# BBiQ-1_2.net
KiCad netlist of a schematic drawn in EAGLE
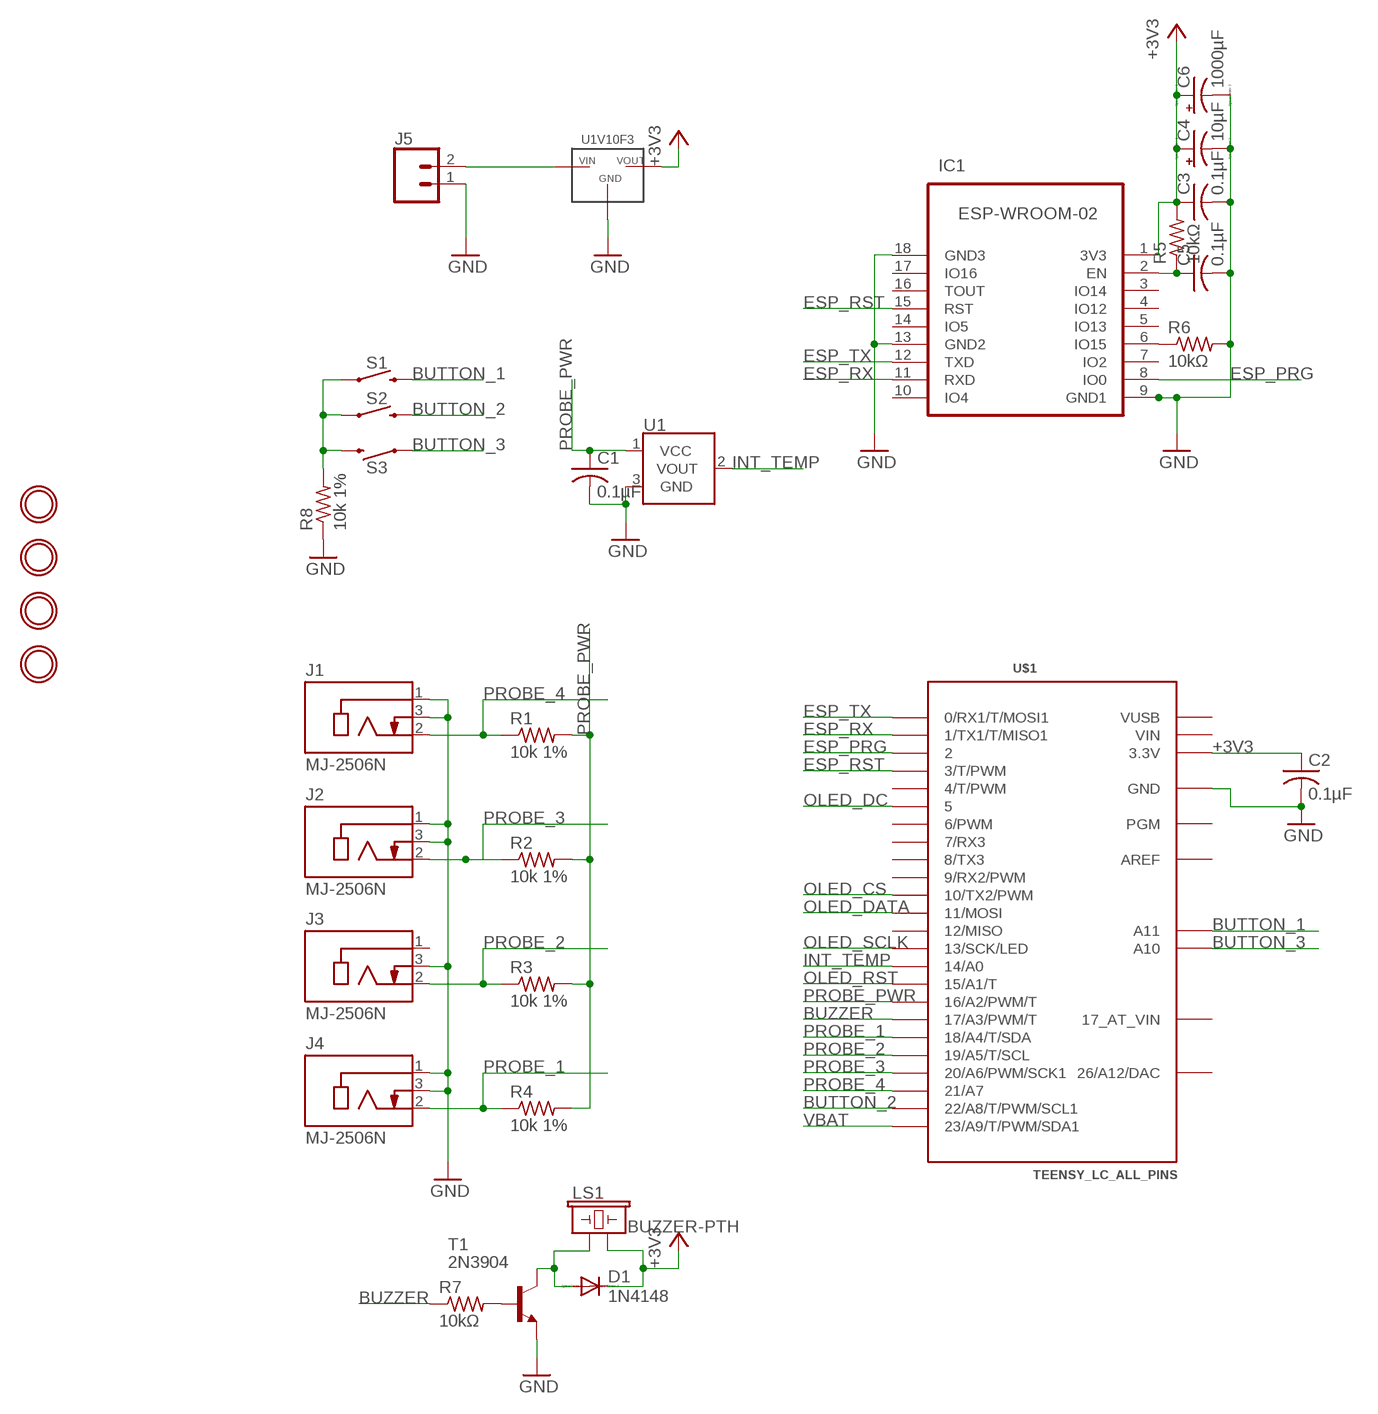
[diagram p0: schematic, sheet 1]

(export (version "E")
  (design (tool "Eeschema 10.0.6"))
  (components
    (comp (ref "C1")
      (value "0.1µF")
      (footprint "eagle-import:C025-025X050")
      (libsource (lib "eagle-import") (part "C-US025-025X050"))
    )
    (comp (ref "C2")
      (value "0.1µF")
      (footprint "eagle-import:C025-025X050")
      (libsource (lib "eagle-import") (part "C-US025-025X050"))
    )
    (comp (ref "C3")
      (value "0.1µF")
      (footprint "eagle-import:C025-025X050")
      (libsource (lib "eagle-import") (part "C-US025-025X050"))
    )
    (comp (ref "C4")
      (value "10µF")
      (footprint "eagle-import:E2-5")
      (libsource (lib "eagle-import") (part "CPOL-USE2-5"))
    )
    (comp (ref "C5")
      (value "0.1µF")
      (footprint "eagle-import:C025-025X050")
      (libsource (lib "eagle-import") (part "C-US025-025X050"))
    )
    (comp (ref "C6")
      (value "1000µF")
      (footprint "eagle-import:E3,5-8")
      (libsource (lib "eagle-import") (part "CPOL-USE3.5-8"))
    )
    (comp (ref "D1")
      (value "1N4148")
      (footprint "eagle-import:DO35-7")
      (libsource (lib "eagle-import") (part "1N4148DO35-7"))
    )
    (comp (ref "IC1")
      (value "ESP-WROOM-02")
      (footprint "eagle-import:ESP-WROOM-02")
      (libsource (lib "eagle-import") (part "ESP-WROOM-02"))
    )
    (comp (ref "J1")
      (value "MJ-2506N")
      (footprint "eagle-import:CUI_MJ-2506N")
      (fields (field (name "MANUFACTURER") "CUI INC"))
      (libsource (lib "eagle-import") (part "MJ-2506N"))
    )
    (comp (ref "J2")
      (value "MJ-2506N")
      (footprint "eagle-import:CUI_MJ-2506N")
      (fields (field (name "MANUFACTURER") "CUI INC"))
      (libsource (lib "eagle-import") (part "MJ-2506N"))
    )
    (comp (ref "J3")
      (value "MJ-2506N")
      (footprint "eagle-import:CUI_MJ-2506N")
      (fields (field (name "MANUFACTURER") "CUI INC"))
      (libsource (lib "eagle-import") (part "MJ-2506N"))
    )
    (comp (ref "J4")
      (value "MJ-2506N")
      (footprint "eagle-import:CUI_MJ-2506N")
      (fields (field (name "MANUFACTURER") "CUI INC"))
      (libsource (lib "eagle-import") (part "MJ-2506N"))
    )
    (comp (ref "J5")
      (value "CONN_02JST-PTH-2")
      (footprint "eagle-import:JST-2-PTH")
      (libsource (lib "eagle-import") (part "CONN_02JST-PTH-2"))
    )
    (comp (ref "LS1")
      (value "BUZZER-PTH")
      (footprint "eagle-import:BUZZER-12MM")
      (libsource (lib "eagle-import") (part "BUZZER-PTH"))
    )
    (comp (ref "R1")
      (value "10k 1%")
      (footprint "eagle-import:0207_7")
      (libsource (lib "eagle-import") (part "R-US_0207/7"))
    )
    (comp (ref "R2")
      (value "10k 1%")
      (footprint "eagle-import:0207_7")
      (libsource (lib "eagle-import") (part "R-US_0207/7"))
    )
    (comp (ref "R3")
      (value "10k 1%")
      (footprint "eagle-import:0207_7")
      (libsource (lib "eagle-import") (part "R-US_0207/7"))
    )
    (comp (ref "R4")
      (value "10k 1%")
      (footprint "eagle-import:0207_7")
      (libsource (lib "eagle-import") (part "R-US_0207/7"))
    )
    (comp (ref "R5")
      (value "10kΩ")
      (footprint "eagle-import:0207_7")
      (libsource (lib "eagle-import") (part "R-US_0207/7"))
    )
    (comp (ref "R6")
      (value "10kΩ")
      (footprint "eagle-import:0207_7")
      (libsource (lib "eagle-import") (part "R-US_0207/7"))
    )
    (comp (ref "R7")
      (value "10kΩ")
      (footprint "eagle-import:0207_7")
      (libsource (lib "eagle-import") (part "R-US_0207/7"))
    )
    (comp (ref "R8")
      (value "10k 1%")
      (footprint "eagle-import:0207_7")
      (libsource (lib "eagle-import") (part "R-US_0207/7"))
    )
    (comp (ref "S1")
      (value "MOMENTARY-SWITCH-SPST-PTH-6.0MM")
      (footprint "eagle-import:TACTILE_SWITCH_PTH_6.0MM")
      (libsource (lib "eagle-import") (part "MOMENTARY-SWITCH-SPST-PTH-6.0MM"))
    )
    (comp (ref "S2")
      (value "MOMENTARY-SWITCH-SPST-PTH-6.0MM")
      (footprint "eagle-import:TACTILE_SWITCH_PTH_6.0MM")
      (libsource (lib "eagle-import") (part "MOMENTARY-SWITCH-SPST-PTH-6.0MM"))
    )
    (comp (ref "S3")
      (value "MOMENTARY-SWITCH-SPST-PTH-6.0MM")
      (footprint "eagle-import:TACTILE_SWITCH_PTH_6.0MM")
      (libsource (lib "eagle-import") (part "MOMENTARY-SWITCH-SPST-PTH-6.0MM"))
    )
    (comp (ref "T1")
      (value "2N3904")
      (footprint "eagle-import:TO92")
      (libsource (lib "eagle-import") (part "2N3904"))
    )
    (comp (ref "U$1")
      (value "TEENSY_LC_ALL_PINS")
      (footprint "eagle-import:TEENSY_3.0-3.2&LC_ALL_PINS")
      (libsource (lib "eagle-import") (part "TEENSY_LC_ALL_PINS"))
    )
    (comp (ref "U$2")
      (value "U1V10F3")
      (footprint "eagle-import:U1V10F3")
      (libsource (lib "eagle-import") (part "U1V10F3"))
    )
    (comp (ref "U$3")
      (value "MOUNTINGHOLE2.5")
      (footprint "eagle-import:MOUNTINGHOLE_2.5_PLATED")
      (libsource (lib "eagle-import") (part "MOUNTINGHOLE2.5"))
    )
    (comp (ref "U$4")
      (value "MOUNTINGHOLE2.5")
      (footprint "eagle-import:MOUNTINGHOLE_2.5_PLATED")
      (libsource (lib "eagle-import") (part "MOUNTINGHOLE2.5"))
    )
    (comp (ref "U$5")
      (value "MOUNTINGHOLE2.5")
      (footprint "eagle-import:MOUNTINGHOLE_2.5_PLATED")
      (libsource (lib "eagle-import") (part "MOUNTINGHOLE2.5"))
    )
    (comp (ref "U$6")
      (value "MOUNTINGHOLE2.5")
      (footprint "eagle-import:MOUNTINGHOLE_2.5_PLATED")
      (libsource (lib "eagle-import") (part "MOUNTINGHOLE2.5"))
    )
    (comp (ref "U1")
      (value "TMP36GT9")
      (footprint "eagle-import:TO-92")
      (libsource (lib "eagle-import") (part "TMP36GT9"))
    )
  )
  (nets
    (net (code "1") (name "+3V3") (class "Default")
      (node (ref "C2") (pin "1") (pinfunction "1_1") (pintype "passive"))
      (node (ref "C3") (pin "1") (pinfunction "1_1") (pintype "passive"))
      (node (ref "C4") (pin "+") (pinfunction "+_+") (pintype "passive"))
      (node (ref "C6") (pin "+") (pinfunction "+_+") (pintype "passive"))
      (node (ref "D1") (pin "C") (pinfunction "C_C") (pintype "passive"))
      (node (ref "IC1") (pin "1") (pinfunction "3V3_1") (pintype "power_in"))
      (node (ref "LS1") (pin "-") (pinfunction "2_-") (pintype "passive"))
      (node (ref "R5") (pin "2") (pinfunction "2_2") (pintype "passive"))
      (node (ref "U$1") (pin "3.3V") (pinfunction "3.3V_3.3V") (pintype "power_in"))
      (node (ref "U$1") (pin "3.3V1") (pinfunction "3.3V_3.3V1") (pintype "power_in"))
      (node (ref "U$2") (pin "VOUT") (pinfunction "VOUT_VOUT") (pintype "bidirectional"))
    )
    (net (code "2") (name "/26{slash}A12{slash}DAC") (class "Default")
      (node (ref "U$1") (pin "RESET/DAC") (pinfunction "26/A12/DAC_RESET/DAC") (pintype "power_in"))
    )
    (net (code "3") (name "/AREF") (class "Default")
      (node (ref "U$1") (pin "AREF") (pinfunction "AREF_AREF") (pintype "power_in"))
    )
    (net (code "4") (name "/BUTTON_1") (class "Default")
      (node (ref "S1") (pin "3") (pinfunction "2_3") (pintype "passive"))
      (node (ref "U$1") (pin "A11") (pinfunction "A11_A11") (pintype "bidirectional"))
    )
    (net (code "5") (name "/BUTTON_2") (class "Default")
      (node (ref "S2") (pin "3") (pinfunction "2_3") (pintype "passive"))
      (node (ref "U$1") (pin "22/A8") (pinfunction "22/A8/T/PWM/SCL1_22/A8") (pintype "bidirectional"))
    )
    (net (code "6") (name "/BUTTON_3") (class "Default")
      (node (ref "S3") (pin "1") (pinfunction "1_1") (pintype "passive"))
      (node (ref "U$1") (pin "A10") (pinfunction "A10_A10") (pintype "bidirectional"))
    )
    (net (code "7") (name "/BUZZER") (class "Default")
      (node (ref "R7") (pin "1") (pinfunction "1_1") (pintype "passive"))
      (node (ref "U$1") (pin "17/A3") (pinfunction "17/A3/PWM/T_17/A3") (pintype "bidirectional"))
    )
    (net (code "8") (name "/ESP_PRG") (class "Default")
      (node (ref "IC1") (pin "8") (pinfunction "IO0_8") (pintype "bidirectional"))
      (node (ref "U$1") (pin "2") (pinfunction "2_2") (pintype "bidirectional"))
    )
    (net (code "9") (name "/ESP_RST") (class "Default")
      (node (ref "IC1") (pin "15") (pinfunction "RST_15") (pintype "bidirectional"))
      (node (ref "U$1") (pin "3") (pinfunction "3/T/PWM_3") (pintype "bidirectional"))
    )
    (net (code "10") (name "/ESP_RX") (class "Default")
      (node (ref "IC1") (pin "11") (pinfunction "RXD_11") (pintype "bidirectional"))
      (node (ref "U$1") (pin "1") (pinfunction "1/TX1/T/MISO1_1") (pintype "bidirectional"))
    )
    (net (code "11") (name "/ESP_TX") (class "Default")
      (node (ref "IC1") (pin "12") (pinfunction "TXD_12") (pintype "bidirectional"))
      (node (ref "U$1") (pin "0") (pinfunction "0/RX1/T/MOSI1_0") (pintype "bidirectional"))
    )
    (net (code "12") (name "/INT_TEMP") (class "Default")
      (node (ref "U$1") (pin "14/A0") (pinfunction "14/A0_14/A0") (pintype "bidirectional"))
      (node (ref "U1") (pin "2") (pinfunction "VOUT_2") (pintype "bidirectional"))
    )
    (net (code "13") (name "/OLED_CS") (class "Default")
      (node (ref "U$1") (pin "10") (pinfunction "10/TX2/PWM_10") (pintype "bidirectional"))
    )
    (net (code "14") (name "/OLED_DATA") (class "Default")
      (node (ref "U$1") (pin "11") (pinfunction "11/MOSI_11") (pintype "bidirectional"))
    )
    (net (code "15") (name "/OLED_DC") (class "Default")
      (node (ref "U$1") (pin "5") (pinfunction "5_5") (pintype "bidirectional"))
    )
    (net (code "16") (name "/OLED_RST") (class "Default")
      (node (ref "U$1") (pin "15/A1") (pinfunction "15/A1/T_15/A1") (pintype "bidirectional"))
    )
    (net (code "17") (name "/OLED_SCLK") (class "Default")
      (node (ref "U$1") (pin "13") (pinfunction "13/SCK/LED_13") (pintype "bidirectional"))
    )
    (net (code "18") (name "/PROBE_1") (class "Default")
      (node (ref "J4") (pin "2") (pinfunction "2_2") (pintype "passive"))
      (node (ref "R4") (pin "1") (pinfunction "1_1") (pintype "passive"))
      (node (ref "U$1") (pin "18/A4") (pinfunction "18/A4/T/SDA_18/A4") (pintype "bidirectional"))
    )
    (net (code "19") (name "/PROBE_2") (class "Default")
      (node (ref "J3") (pin "2") (pinfunction "2_2") (pintype "passive"))
      (node (ref "R3") (pin "1") (pinfunction "1_1") (pintype "passive"))
      (node (ref "U$1") (pin "19/A5") (pinfunction "19/A5/T/SCL_19/A5") (pintype "bidirectional"))
    )
    (net (code "20") (name "/PROBE_3") (class "Default")
      (node (ref "J2") (pin "2") (pinfunction "2_2") (pintype "passive"))
      (node (ref "R2") (pin "1") (pinfunction "1_1") (pintype "passive"))
      (node (ref "U$1") (pin "20/A6") (pinfunction "20/A6/PWM/SCK1_20/A6") (pintype "bidirectional"))
    )
    (net (code "21") (name "/PROBE_4") (class "Default")
      (node (ref "J1") (pin "2") (pinfunction "2_2") (pintype "passive"))
      (node (ref "R1") (pin "1") (pinfunction "1_1") (pintype "passive"))
      (node (ref "U$1") (pin "21/A7") (pinfunction "21/A7_21/A7") (pintype "bidirectional"))
    )
    (net (code "22") (name "/PROBE_PWR") (class "Default")
      (node (ref "C1") (pin "1") (pinfunction "1_1") (pintype "passive"))
      (node (ref "R1") (pin "2") (pinfunction "2_2") (pintype "passive"))
      (node (ref "R2") (pin "2") (pinfunction "2_2") (pintype "passive"))
      (node (ref "R3") (pin "2") (pinfunction "2_2") (pintype "passive"))
      (node (ref "R4") (pin "2") (pinfunction "2_2") (pintype "passive"))
      (node (ref "U$1") (pin "16/A2") (pinfunction "16/A2/PWM/T_16/A2") (pintype "bidirectional"))
      (node (ref "U1") (pin "1") (pinfunction "VCC_1") (pintype "bidirectional"))
    )
    (net (code "23") (name "/VBAT") (class "Default")
      (node (ref "J5") (pin "2") (pinfunction "2_2") (pintype "passive"))
      (node (ref "U$1") (pin "23/A9") (pinfunction "23/A9/T/PWM/SDA1_23/A9") (pintype "bidirectional"))
      (node (ref "U$2") (pin "VIN") (pinfunction "VIN_VIN") (pintype "bidirectional"))
    )
    (net (code "24") (name "/VIN") (class "Default")
      (node (ref "U$1") (pin "VIN") (pinfunction "VIN_VIN") (pintype "power_in"))
    )
    (net (code "25") (name "/VUSB") (class "Default")
      (node (ref "U$1") (pin "VUSB") (pinfunction "VUSB_VUSB") (pintype "power_in"))
    )
    (net (code "26") (name "GND") (class "Default")
      (node (ref "C1") (pin "2") (pinfunction "2_2") (pintype "passive"))
      (node (ref "C2") (pin "2") (pinfunction "2_2") (pintype "passive"))
      (node (ref "C3") (pin "2") (pinfunction "2_2") (pintype "passive"))
      (node (ref "C4") (pin "-") (pinfunction "-_-") (pintype "passive"))
      (node (ref "C5") (pin "2") (pinfunction "2_2") (pintype "passive"))
      (node (ref "C6") (pin "-") (pinfunction "-_-") (pintype "passive"))
      (node (ref "IC1") (pin "13") (pinfunction "GND2_13") (pintype "power_in"))
      (node (ref "IC1") (pin "18") (pinfunction "GND3_18") (pintype "power_in"))
      (node (ref "IC1") (pin "19") (pinfunction "GND0_19") (pintype "power_in"))
      (node (ref "IC1") (pin "9") (pinfunction "GND1_9") (pintype "power_in"))
      (node (ref "J1") (pin "1") (pinfunction "1_1") (pintype "passive"))
      (node (ref "J1") (pin "3") (pinfunction "3_3") (pintype "passive"))
      (node (ref "J2") (pin "1") (pinfunction "1_1") (pintype "passive"))
      (node (ref "J2") (pin "3") (pinfunction "3_3") (pintype "passive"))
      (node (ref "J3") (pin "3") (pinfunction "3_3") (pintype "passive"))
      (node (ref "J4") (pin "1") (pinfunction "1_1") (pintype "passive"))
      (node (ref "J4") (pin "3") (pinfunction "3_3") (pintype "passive"))
      (node (ref "J5") (pin "1") (pinfunction "1_1") (pintype "passive"))
      (node (ref "R6") (pin "2") (pinfunction "2_2") (pintype "passive"))
      (node (ref "R8") (pin "1") (pinfunction "1_1") (pintype "passive"))
      (node (ref "T1") (pin "3") (pinfunction "E_3") (pintype "passive"))
      (node (ref "U$1") (pin "AGND") (pinfunction "GND_AGND") (pintype "power_in"))
      (node (ref "U$1") (pin "GND") (pinfunction "GND_GND") (pintype "power_in"))
      (node (ref "U$1") (pin "GND1") (pinfunction "GND_GND1") (pintype "power_in"))
      (node (ref "U$2") (pin "GND") (pinfunction "GND_GND") (pintype "bidirectional"))
      (node (ref "U1") (pin "3") (pinfunction "GND_3") (pintype "bidirectional"))
    )
    (net (code "27") (name "Net-(IC1-EN)") (class "Default")
      (node (ref "C5") (pin "1") (pinfunction "1_1") (pintype "passive"))
      (node (ref "IC1") (pin "2") (pinfunction "EN_2") (pintype "bidirectional"))
      (node (ref "R5") (pin "1") (pinfunction "1_1") (pintype "passive"))
    )
    (net (code "28") (name "Net-(IC1-IO15)") (class "Default")
      (node (ref "IC1") (pin "6") (pinfunction "IO15_6") (pintype "bidirectional"))
      (node (ref "R6") (pin "1") (pinfunction "1_1") (pintype "passive"))
    )
    (net (code "29") (name "Net-(LS1-1)") (class "Default")
      (node (ref "D1") (pin "A") (pinfunction "A_A") (pintype "passive"))
      (node (ref "LS1") (pin "+") (pinfunction "1_+") (pintype "passive"))
      (node (ref "T1") (pin "1") (pinfunction "C_1") (pintype "passive"))
    )
    (net (code "30") (name "Net-(S3-2)") (class "Default")
      (node (ref "R8") (pin "2") (pinfunction "2_2") (pintype "passive"))
      (node (ref "S1") (pin "1") (pinfunction "1_1") (pintype "passive"))
      (node (ref "S2") (pin "1") (pinfunction "1_1") (pintype "passive"))
      (node (ref "S3") (pin "3") (pinfunction "2_3") (pintype "passive"))
    )
    (net (code "31") (name "Net-(T1-B)") (class "Default")
      (node (ref "R7") (pin "2") (pinfunction "2_2") (pintype "passive"))
      (node (ref "T1") (pin "2") (pinfunction "B_2") (pintype "passive"))
    )
    (net (code "32") (name "unconnected-(IC1-IO2-Pad7)") (class "Default")
      (node (ref "IC1") (pin "7") (pinfunction "IO2_7") (pintype "bidirectional"))
    )
    (net (code "33") (name "unconnected-(IC1-IO4-Pad10)") (class "Default")
      (node (ref "IC1") (pin "10") (pinfunction "IO4_10") (pintype "bidirectional"))
    )
    (net (code "34") (name "unconnected-(IC1-IO5-Pad14)") (class "Default")
      (node (ref "IC1") (pin "14") (pinfunction "IO5_14") (pintype "open_collector"))
    )
    (net (code "35") (name "unconnected-(IC1-IO12-Pad4)") (class "Default")
      (node (ref "IC1") (pin "4") (pinfunction "IO12_4") (pintype "bidirectional"))
    )
    (net (code "36") (name "unconnected-(IC1-IO13-Pad5)") (class "Default")
      (node (ref "IC1") (pin "5") (pinfunction "IO13_5") (pintype "bidirectional"))
    )
    (net (code "37") (name "unconnected-(IC1-IO14-Pad3)") (class "Default")
      (node (ref "IC1") (pin "3") (pinfunction "IO14_3") (pintype "bidirectional"))
    )
    (net (code "38") (name "unconnected-(IC1-IO16-Pad17)") (class "Default")
      (node (ref "IC1") (pin "17") (pinfunction "IO16_17") (pintype "bidirectional"))
    )
    (net (code "39") (name "unconnected-(IC1-TOUT-Pad16)") (class "Default")
      (node (ref "IC1") (pin "16") (pinfunction "TOUT_16") (pintype "bidirectional"))
    )
    (net (code "40") (name "unconnected-(J3-Pad1)") (class "Default")
      (node (ref "J3") (pin "1") (pinfunction "1_1") (pintype "passive"))
    )
    (net (code "41") (name "unconnected-(U$1-4{slash}T{slash}PWM-Pad4)") (class "Default")
      (node (ref "U$1") (pin "4") (pinfunction "4/T/PWM_4") (pintype "bidirectional"))
    )
    (net (code "42") (name "unconnected-(U$1-6{slash}PWM-Pad6)") (class "Default")
      (node (ref "U$1") (pin "6") (pinfunction "6/PWM_6") (pintype "bidirectional"))
    )
    (net (code "43") (name "unconnected-(U$1-7{slash}RX3-Pad7)") (class "Default")
      (node (ref "U$1") (pin "7") (pinfunction "7/RX3_7") (pintype "bidirectional"))
    )
    (net (code "44") (name "unconnected-(U$1-8{slash}TX3-Pad8)") (class "Default")
      (node (ref "U$1") (pin "8") (pinfunction "8/TX3_8") (pintype "bidirectional"))
    )
    (net (code "45") (name "unconnected-(U$1-9{slash}RX2{slash}PWM-Pad9)") (class "Default")
      (node (ref "U$1") (pin "9") (pinfunction "9/RX2/PWM_9") (pintype "bidirectional"))
    )
    (net (code "46") (name "unconnected-(U$1-12{slash}MISO-Pad12)") (class "Default")
      (node (ref "U$1") (pin "12") (pinfunction "12/MISO_12") (pintype "bidirectional"))
    )
    (net (code "47") (name "unconnected-(U$1-17_AT_VIN-PadVBAT)") (class "Default")
      (node (ref "U$1") (pin "VBAT") (pinfunction "17_AT_VIN_VBAT") (pintype "bidirectional"))
    )
    (net (code "48") (name "unconnected-(U$1-PadPGM)") (class "Default")
      (node (ref "U$1") (pin "PGM") (pinfunction "PGM_PGM") (pintype "bidirectional"))
    )
  )
)
